# FIT_TCM_SFP_PLUS.net
KiCad netlist of a schematic drawn in Altium Designer
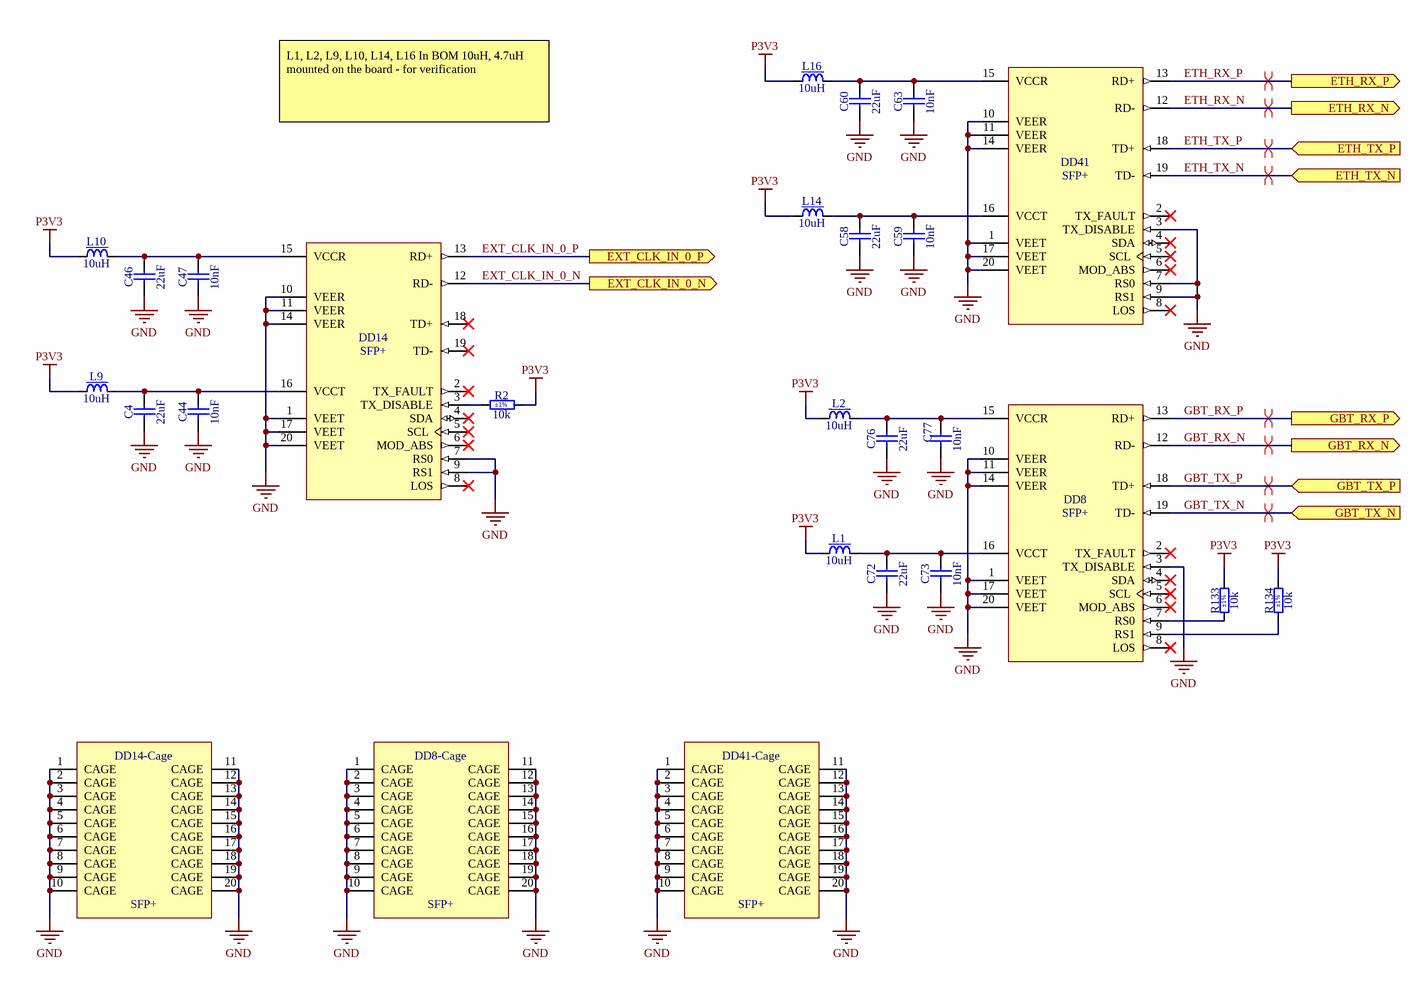
[diagram p0: FIT_TCM_SFP_PLUS.SchDoc]

(export (version "E")
  (design (tool "Eeschema 10.0.6"))
  (components
    (comp (ref "C4")
      (value "22uF")
      (footprint "CAPC3216X180N")
      (description "Non-polarised capacitor")
      (fields
        (field (name "PART NUMBER") "CC1206_22UF_25V_20%_X5R")
        (field (name "VOLTAGE") "25V")
        (field (name "AUTHOR") "CERN DEM WB")
      )
      (libsource (lib "Capacitors") (part "Capacitor - non polarized"))
    )
    (comp (ref "C44")
      (value "10nF")
      (footprint "CAPC2012X135N")
      (description "Non-polarised capacitor")
      (fields
        (field (name "PART NUMBER") "CC0805_10NF_50V_10%_X7R")
        (field (name "VOLTAGE") "50V")
        (field (name "AUTHOR") "CERN DEM JLC")
      )
      (libsource (lib "Capacitors") (part "Capacitor - non polarized"))
    )
    (comp (ref "C46")
      (value "22uF")
      (footprint "CAPC3216X180N")
      (description "Non-polarised capacitor")
      (fields
        (field (name "PART NUMBER") "CC1206_22UF_25V_20%_X5R")
        (field (name "VOLTAGE") "25V")
        (field (name "AUTHOR") "CERN DEM WB")
      )
      (libsource (lib "Capacitors") (part "Capacitor - non polarized"))
    )
    (comp (ref "C47")
      (value "10nF")
      (footprint "CAPC2012X135N")
      (description "Non-polarised capacitor")
      (fields
        (field (name "PART NUMBER") "CC0805_10NF_50V_10%_X7R")
        (field (name "VOLTAGE") "50V")
        (field (name "AUTHOR") "CERN DEM JLC")
      )
      (libsource (lib "Capacitors") (part "Capacitor - non polarized"))
    )
    (comp (ref "C58")
      (value "22uF")
      (footprint "CAPC3216X180N")
      (description "Non-polarised capacitor")
      (fields
        (field (name "PART NUMBER") "CC1206_22UF_25V_20%_X5R")
        (field (name "VOLTAGE") "25V")
        (field (name "AUTHOR") "CERN DEM WB")
      )
      (libsource (lib "Capacitors") (part "Capacitor - non polarized"))
    )
    (comp (ref "C59")
      (value "10nF")
      (footprint "CAPC2012X135N")
      (description "Non-polarised capacitor")
      (fields
        (field (name "PART NUMBER") "CC0805_10NF_50V_10%_X7R")
        (field (name "VOLTAGE") "50V")
        (field (name "AUTHOR") "CERN DEM JLC")
      )
      (libsource (lib "Capacitors") (part "Capacitor - non polarized"))
    )
    (comp (ref "C60")
      (value "22uF")
      (footprint "CAPC3216X180N")
      (description "Non-polarised capacitor")
      (fields
        (field (name "PART NUMBER") "CC1206_22UF_25V_20%_X5R")
        (field (name "VOLTAGE") "25V")
        (field (name "AUTHOR") "CERN DEM WB")
      )
      (libsource (lib "Capacitors") (part "Capacitor - non polarized"))
    )
    (comp (ref "C63")
      (value "10nF")
      (footprint "CAPC2012X135N")
      (description "Non-polarised capacitor")
      (fields
        (field (name "PART NUMBER") "CC0805_10NF_50V_10%_X7R")
        (field (name "VOLTAGE") "50V")
        (field (name "AUTHOR") "CERN DEM JLC")
      )
      (libsource (lib "Capacitors") (part "Capacitor - non polarized"))
    )
    (comp (ref "C72")
      (value "22uF")
      (footprint "CAPC3216X180N")
      (description "Non-polarised capacitor")
      (fields
        (field (name "PART NUMBER") "CC1206_22UF_25V_20%_X5R")
        (field (name "VOLTAGE") "25V")
        (field (name "AUTHOR") "CERN DEM WB")
      )
      (libsource (lib "Capacitors") (part "Capacitor - non polarized"))
    )
    (comp (ref "C73")
      (value "10nF")
      (footprint "CAPC2012X135N")
      (description "Non-polarised capacitor")
      (fields
        (field (name "PART NUMBER") "CC0805_10NF_50V_10%_X7R")
        (field (name "VOLTAGE") "50V")
        (field (name "AUTHOR") "CERN DEM JLC")
      )
      (libsource (lib "Capacitors") (part "Capacitor - non polarized"))
    )
    (comp (ref "C76")
      (value "22uF")
      (footprint "CAPC3216X180N")
      (description "Non-polarised capacitor")
      (fields
        (field (name "PART NUMBER") "CC1206_22UF_25V_20%_X5R")
        (field (name "VOLTAGE") "25V")
        (field (name "AUTHOR") "CERN DEM WB")
      )
      (libsource (lib "Capacitors") (part "Capacitor - non polarized"))
    )
    (comp (ref "C77")
      (value "10nF")
      (footprint "CAPC2012X135N")
      (description "Non-polarised capacitor")
      (fields
        (field (name "PART NUMBER") "CC0805_10NF_50V_10%_X7R")
        (field (name "VOLTAGE") "50V")
        (field (name "AUTHOR") "CERN DEM JLC")
      )
      (libsource (lib "Capacitors") (part "Capacitor - non polarized"))
    )
    (comp (ref "DD8")
      (value "SFP+")
      (footprint "AMPHENOL_UE76A203000")
      (description "20 Position SFP+ Connector (Small Form-factor Pluggable)")
      (fields
        (field (name "PART NUMBER") "AMPHENOL_UE76A203000")
        (field (name "MANUFACTURER") "AMPHENOL")
        (field (name "AUTHOR") "CERN DEM BC")
      )
      (libsource (lib "Connectors") (part "SFP+x1"))
    )
    (comp (ref "DD8-Cage")
      (value "SFP+")
      (footprint "AMPHENOL_U77A16131001")
      (description "SFP+ 1x1 Cage (20Pins)")
      (fields
        (field (name "PART NUMBER") "AMPHENOL_U77A16131001")
        (field (name "MANUFACTURER") "AMPHENOL")
        (field (name "AUTHOR") "CERN DEM BC")
      )
      (libsource (lib "Connectors") (part "SFP+ 1x1 Cage (20Pins)"))
    )
    (comp (ref "DD14")
      (value "SFP+")
      (footprint "AMPHENOL_UE76A203000")
      (description "20 Position SFP+ Connector (Small Form-factor Pluggable)")
      (fields
        (field (name "PART NUMBER") "AMPHENOL_UE76A203000")
        (field (name "MANUFACTURER") "AMPHENOL")
        (field (name "AUTHOR") "CERN DEM BC")
      )
      (libsource (lib "Connectors") (part "SFP+x1"))
    )
    (comp (ref "DD14-Cage")
      (value "SFP+")
      (footprint "AMPHENOL_U77A16131001")
      (description "SFP+ 1x1 Cage (20Pins)")
      (fields
        (field (name "PART NUMBER") "AMPHENOL_U77A16131001")
        (field (name "MANUFACTURER") "AMPHENOL")
        (field (name "AUTHOR") "CERN DEM BC")
      )
      (libsource (lib "Connectors") (part "SFP+ 1x1 Cage (20Pins)"))
    )
    (comp (ref "DD41")
      (value "SFP+")
      (footprint "AMPHENOL_UE76A203000")
      (description "20 Position SFP+ Connector (Small Form-factor Pluggable)")
      (fields
        (field (name "PART NUMBER") "AMPHENOL_UE76A203000")
        (field (name "MANUFACTURER") "AMPHENOL")
        (field (name "AUTHOR") "CERN DEM BC")
      )
      (libsource (lib "Connectors") (part "SFP+x1"))
    )
    (comp (ref "DD41-Cage")
      (value "SFP+")
      (footprint "AMPHENOL_U77A16131001")
      (description "SFP+ 1x1 Cage (20Pins)")
      (fields
        (field (name "PART NUMBER") "AMPHENOL_U77A16131001")
        (field (name "MANUFACTURER") "AMPHENOL")
        (field (name "AUTHOR") "CERN DEM BC")
      )
      (libsource (lib "Connectors") (part "SFP+ 1x1 Cage (20Pins)"))
    )
    (comp (ref "L1")
      (value "10uH")
      (footprint "INDM5552X200N")
      (description "Inductor With Core")
      (fields
        (field (name "PART NUMBER") "IND2020_10UH_20%_VISHAY_IHLP-2020BZ-11")
        (field (name "POWER") "2.2A")
        (field (name "AUTHOR") "CERN DEM HF")
      )
      (libsource (lib "Inductors & Transformers") (part "Inductor With Magnetic core"))
    )
    (comp (ref "L2")
      (value "10uH")
      (footprint "INDM5552X200N")
      (description "Inductor With Core")
      (fields
        (field (name "PART NUMBER") "IND2020_10UH_20%_VISHAY_IHLP-2020BZ-11")
        (field (name "POWER") "2.2A")
        (field (name "AUTHOR") "CERN DEM HF")
      )
      (libsource (lib "Inductors & Transformers") (part "Inductor With Magnetic core"))
    )
    (comp (ref "L9")
      (value "10uH")
      (footprint "INDM5552X200N")
      (description "Inductor With Core")
      (fields
        (field (name "PART NUMBER") "IND2020_10UH_20%_VISHAY_IHLP-2020BZ-11")
        (field (name "POWER") "2.2A")
        (field (name "AUTHOR") "CERN DEM HF")
      )
      (libsource (lib "Inductors & Transformers") (part "Inductor With Magnetic core"))
    )
    (comp (ref "L10")
      (value "10uH")
      (footprint "INDM5552X200N")
      (description "Inductor With Core")
      (fields
        (field (name "PART NUMBER") "IND2020_10UH_20%_VISHAY_IHLP-2020BZ-11")
        (field (name "POWER") "2.2A")
        (field (name "AUTHOR") "CERN DEM HF")
      )
      (libsource (lib "Inductors & Transformers") (part "Inductor With Magnetic core"))
    )
    (comp (ref "L14")
      (value "10uH")
      (footprint "INDM5552X200N")
      (description "Inductor With Core")
      (fields
        (field (name "PART NUMBER") "IND2020_10UH_20%_VISHAY_IHLP-2020BZ-11")
        (field (name "POWER") "2.2A")
        (field (name "AUTHOR") "CERN DEM HF")
      )
      (libsource (lib "Inductors & Transformers") (part "Inductor With Magnetic core"))
    )
    (comp (ref "L16")
      (value "10uH")
      (footprint "INDM5552X200N")
      (description "Inductor With Core")
      (fields
        (field (name "PART NUMBER") "IND2020_10UH_20%_VISHAY_IHLP-2020BZ-11")
        (field (name "POWER") "2.2A")
        (field (name "AUTHOR") "CERN DEM HF")
      )
      (libsource (lib "Inductors & Transformers") (part "Inductor With Magnetic core"))
    )
    (comp (ref "R2")
      (value "10k")
      (footprint "RESC2012X60N")
      (description "Resistor - 1%")
      (fields
        (field (name "TOLERANCE") "±1%")
        (field (name "PART NUMBER") "R0805_10K_1%_0.125W_100PPM")
        (field (name "POWER") "0.125W")
        (field (name "AUTHOR") "CERN DEM JLC")
      )
      (libsource (lib "Resistors") (part "Resistor - 1%"))
    )
    (comp (ref "R133")
      (value "10k")
      (footprint "RESC2012X60N")
      (description "Resistor - 1%")
      (fields
        (field (name "TOLERANCE") "±1%")
        (field (name "PART NUMBER") "R0805_10K_1%_0.125W_100PPM")
        (field (name "POWER") "0.125W")
        (field (name "AUTHOR") "CERN DEM JLC")
      )
      (libsource (lib "Resistors") (part "Resistor - 1%"))
    )
    (comp (ref "R134")
      (value "10k")
      (footprint "RESC2012X60N")
      (description "Resistor - 1%")
      (fields
        (field (name "TOLERANCE") "±1%")
        (field (name "PART NUMBER") "R0805_10K_1%_0.125W_100PPM")
        (field (name "POWER") "0.125W")
        (field (name "AUTHOR") "CERN DEM JLC")
      )
      (libsource (lib "Resistors") (part "Resistor - 1%"))
    )
  )
  (nets
    (net (code "1") (name "/ETH_RX_N") (class "Default")
      (node (ref "DD41") (pin "12") (pinfunction "RD-_12") (pintype "output"))
    )
    (net (code "2") (name "/ETH_RX_P") (class "Default")
      (node (ref "DD41") (pin "13") (pinfunction "RD+_13") (pintype "output"))
    )
    (net (code "3") (name "/ETH_TX_N") (class "Default")
      (node (ref "DD41") (pin "19") (pinfunction "TD-_19") (pintype "input"))
    )
    (net (code "4") (name "/ETH_TX_P") (class "Default")
      (node (ref "DD41") (pin "18") (pinfunction "TD+_18") (pintype "input"))
    )
    (net (code "5") (name "/EXT_CLK_IN_0_N") (class "Default")
      (node (ref "DD14") (pin "12") (pinfunction "RD-_12") (pintype "output"))
    )
    (net (code "6") (name "/EXT_CLK_IN_0_P") (class "Default")
      (node (ref "DD14") (pin "13") (pinfunction "RD+_13") (pintype "output"))
    )
    (net (code "7") (name "/GBT_RX_N") (class "Default")
      (node (ref "DD8") (pin "12") (pinfunction "RD-_12") (pintype "output"))
    )
    (net (code "8") (name "/GBT_RX_P") (class "Default")
      (node (ref "DD8") (pin "13") (pinfunction "RD+_13") (pintype "output"))
    )
    (net (code "9") (name "/GBT_TX_N") (class "Default")
      (node (ref "DD8") (pin "19") (pinfunction "TD-_19") (pintype "input"))
    )
    (net (code "10") (name "/GBT_TX_P") (class "Default")
      (node (ref "DD8") (pin "18") (pinfunction "TD+_18") (pintype "input"))
    )
    (net (code "11") (name "GND") (class "Default")
      (node (ref "C4") (pin "1") (pinfunction "1_1") (pintype "passive"))
      (node (ref "C44") (pin "1") (pinfunction "1_1") (pintype "passive"))
      (node (ref "C46") (pin "1") (pinfunction "1_1") (pintype "passive"))
      (node (ref "C47") (pin "1") (pinfunction "1_1") (pintype "passive"))
      (node (ref "C58") (pin "1") (pinfunction "1_1") (pintype "passive"))
      (node (ref "C59") (pin "1") (pinfunction "1_1") (pintype "passive"))
      (node (ref "C60") (pin "1") (pinfunction "1_1") (pintype "passive"))
      (node (ref "C63") (pin "1") (pinfunction "1_1") (pintype "passive"))
      (node (ref "C72") (pin "1") (pinfunction "1_1") (pintype "passive"))
      (node (ref "C73") (pin "1") (pinfunction "1_1") (pintype "passive"))
      (node (ref "C76") (pin "1") (pinfunction "1_1") (pintype "passive"))
      (node (ref "C77") (pin "1") (pinfunction "1_1") (pintype "passive"))
      (node (ref "DD14") (pin "1") (pinfunction "VEET_1") (pintype "power_in"))
      (node (ref "DD14") (pin "10") (pinfunction "VEER_10") (pintype "power_in"))
      (node (ref "DD14") (pin "11") (pinfunction "VEER_11") (pintype "power_in"))
      (node (ref "DD14") (pin "14") (pinfunction "VEER_14") (pintype "power_in"))
      (node (ref "DD14") (pin "17") (pinfunction "VEET_17") (pintype "power_in"))
      (node (ref "DD14") (pin "20") (pinfunction "VEET_20") (pintype "power_in"))
      (node (ref "DD14") (pin "7") (pinfunction "RS0_7") (pintype "input"))
      (node (ref "DD14") (pin "9") (pinfunction "RS1_9") (pintype "input"))
      (node (ref "DD14-Cage") (pin "1") (pinfunction "CAGE_1") (pintype "power_in"))
      (node (ref "DD14-Cage") (pin "10") (pinfunction "CAGE_10") (pintype "power_in"))
      (node (ref "DD14-Cage") (pin "11") (pinfunction "CAGE_11") (pintype "power_in"))
      (node (ref "DD14-Cage") (pin "12") (pinfunction "CAGE_12") (pintype "power_in"))
      (node (ref "DD14-Cage") (pin "13") (pinfunction "CAGE_13") (pintype "power_in"))
      (node (ref "DD14-Cage") (pin "14") (pinfunction "CAGE_14") (pintype "power_in"))
      (node (ref "DD14-Cage") (pin "15") (pinfunction "CAGE_15") (pintype "power_in"))
      (node (ref "DD14-Cage") (pin "16") (pinfunction "CAGE_16") (pintype "power_in"))
      (node (ref "DD14-Cage") (pin "17") (pinfunction "CAGE_17") (pintype "power_in"))
      (node (ref "DD14-Cage") (pin "18") (pinfunction "CAGE_18") (pintype "power_in"))
      (node (ref "DD14-Cage") (pin "19") (pinfunction "CAGE_19") (pintype "power_in"))
      (node (ref "DD14-Cage") (pin "2") (pinfunction "CAGE_2") (pintype "power_in"))
      (node (ref "DD14-Cage") (pin "20") (pinfunction "CAGE_20") (pintype "power_in"))
      (node (ref "DD14-Cage") (pin "3") (pinfunction "CAGE_3") (pintype "power_in"))
      (node (ref "DD14-Cage") (pin "4") (pinfunction "CAGE_4") (pintype "power_in"))
      (node (ref "DD14-Cage") (pin "5") (pinfunction "CAGE_5") (pintype "power_in"))
      (node (ref "DD14-Cage") (pin "6") (pinfunction "CAGE_6") (pintype "power_in"))
      (node (ref "DD14-Cage") (pin "7") (pinfunction "CAGE_7") (pintype "power_in"))
      (node (ref "DD14-Cage") (pin "8") (pinfunction "CAGE_8") (pintype "power_in"))
      (node (ref "DD14-Cage") (pin "9") (pinfunction "CAGE_9") (pintype "power_in"))
      (node (ref "DD41") (pin "1") (pinfunction "VEET_1") (pintype "power_in"))
      (node (ref "DD41") (pin "10") (pinfunction "VEER_10") (pintype "power_in"))
      (node (ref "DD41") (pin "11") (pinfunction "VEER_11") (pintype "power_in"))
      (node (ref "DD41") (pin "14") (pinfunction "VEER_14") (pintype "power_in"))
      (node (ref "DD41") (pin "17") (pinfunction "VEET_17") (pintype "power_in"))
      (node (ref "DD41") (pin "20") (pinfunction "VEET_20") (pintype "power_in"))
      (node (ref "DD41") (pin "3") (pinfunction "TX_DISABLE_3") (pintype "input"))
      (node (ref "DD41") (pin "7") (pinfunction "RS0_7") (pintype "input"))
      (node (ref "DD41") (pin "9") (pinfunction "RS1_9") (pintype "input"))
      (node (ref "DD41-Cage") (pin "1") (pinfunction "CAGE_1") (pintype "power_in"))
      (node (ref "DD41-Cage") (pin "10") (pinfunction "CAGE_10") (pintype "power_in"))
      (node (ref "DD41-Cage") (pin "11") (pinfunction "CAGE_11") (pintype "power_in"))
      (node (ref "DD41-Cage") (pin "12") (pinfunction "CAGE_12") (pintype "power_in"))
      (node (ref "DD41-Cage") (pin "13") (pinfunction "CAGE_13") (pintype "power_in"))
      (node (ref "DD41-Cage") (pin "14") (pinfunction "CAGE_14") (pintype "power_in"))
      (node (ref "DD41-Cage") (pin "15") (pinfunction "CAGE_15") (pintype "power_in"))
      (node (ref "DD41-Cage") (pin "16") (pinfunction "CAGE_16") (pintype "power_in"))
      (node (ref "DD41-Cage") (pin "17") (pinfunction "CAGE_17") (pintype "power_in"))
      (node (ref "DD41-Cage") (pin "18") (pinfunction "CAGE_18") (pintype "power_in"))
      (node (ref "DD41-Cage") (pin "19") (pinfunction "CAGE_19") (pintype "power_in"))
      (node (ref "DD41-Cage") (pin "2") (pinfunction "CAGE_2") (pintype "power_in"))
      (node (ref "DD41-Cage") (pin "20") (pinfunction "CAGE_20") (pintype "power_in"))
      (node (ref "DD41-Cage") (pin "3") (pinfunction "CAGE_3") (pintype "power_in"))
      (node (ref "DD41-Cage") (pin "4") (pinfunction "CAGE_4") (pintype "power_in"))
      (node (ref "DD41-Cage") (pin "5") (pinfunction "CAGE_5") (pintype "power_in"))
      (node (ref "DD41-Cage") (pin "6") (pinfunction "CAGE_6") (pintype "power_in"))
      (node (ref "DD41-Cage") (pin "7") (pinfunction "CAGE_7") (pintype "power_in"))
      (node (ref "DD41-Cage") (pin "8") (pinfunction "CAGE_8") (pintype "power_in"))
      (node (ref "DD41-Cage") (pin "9") (pinfunction "CAGE_9") (pintype "power_in"))
      (node (ref "DD8") (pin "1") (pinfunction "VEET_1") (pintype "power_in"))
      (node (ref "DD8") (pin "10") (pinfunction "VEER_10") (pintype "power_in"))
      (node (ref "DD8") (pin "11") (pinfunction "VEER_11") (pintype "power_in"))
      (node (ref "DD8") (pin "14") (pinfunction "VEER_14") (pintype "power_in"))
      (node (ref "DD8") (pin "17") (pinfunction "VEET_17") (pintype "power_in"))
      (node (ref "DD8") (pin "20") (pinfunction "VEET_20") (pintype "power_in"))
      (node (ref "DD8") (pin "3") (pinfunction "TX_DISABLE_3") (pintype "input"))
      (node (ref "DD8-Cage") (pin "1") (pinfunction "CAGE_1") (pintype "power_in"))
      (node (ref "DD8-Cage") (pin "10") (pinfunction "CAGE_10") (pintype "power_in"))
      (node (ref "DD8-Cage") (pin "11") (pinfunction "CAGE_11") (pintype "power_in"))
      (node (ref "DD8-Cage") (pin "12") (pinfunction "CAGE_12") (pintype "power_in"))
      (node (ref "DD8-Cage") (pin "13") (pinfunction "CAGE_13") (pintype "power_in"))
      (node (ref "DD8-Cage") (pin "14") (pinfunction "CAGE_14") (pintype "power_in"))
      (node (ref "DD8-Cage") (pin "15") (pinfunction "CAGE_15") (pintype "power_in"))
      (node (ref "DD8-Cage") (pin "16") (pinfunction "CAGE_16") (pintype "power_in"))
      (node (ref "DD8-Cage") (pin "17") (pinfunction "CAGE_17") (pintype "power_in"))
      (node (ref "DD8-Cage") (pin "18") (pinfunction "CAGE_18") (pintype "power_in"))
      (node (ref "DD8-Cage") (pin "19") (pinfunction "CAGE_19") (pintype "power_in"))
      (node (ref "DD8-Cage") (pin "2") (pinfunction "CAGE_2") (pintype "power_in"))
      (node (ref "DD8-Cage") (pin "20") (pinfunction "CAGE_20") (pintype "power_in"))
      (node (ref "DD8-Cage") (pin "3") (pinfunction "CAGE_3") (pintype "power_in"))
      (node (ref "DD8-Cage") (pin "4") (pinfunction "CAGE_4") (pintype "power_in"))
      (node (ref "DD8-Cage") (pin "5") (pinfunction "CAGE_5") (pintype "power_in"))
      (node (ref "DD8-Cage") (pin "6") (pinfunction "CAGE_6") (pintype "power_in"))
      (node (ref "DD8-Cage") (pin "7") (pinfunction "CAGE_7") (pintype "power_in"))
      (node (ref "DD8-Cage") (pin "8") (pinfunction "CAGE_8") (pintype "power_in"))
      (node (ref "DD8-Cage") (pin "9") (pinfunction "CAGE_9") (pintype "power_in"))
    )
    (net (code "12") (name "Net-(DD8-RS0)") (class "Default")
      (node (ref "DD8") (pin "7") (pinfunction "RS0_7") (pintype "input"))
      (node (ref "R133") (pin "1") (pinfunction "1_1") (pintype "passive"))
    )
    (net (code "13") (name "Net-(DD8-RS1)") (class "Default")
      (node (ref "DD8") (pin "9") (pinfunction "RS1_9") (pintype "input"))
      (node (ref "R134") (pin "1") (pinfunction "1_1") (pintype "passive"))
    )
    (net (code "14") (name "Net-(DD8-VCCR)") (class "Default")
      (node (ref "C76") (pin "2") (pinfunction "2_2") (pintype "passive"))
      (node (ref "C77") (pin "2") (pinfunction "2_2") (pintype "passive"))
      (node (ref "DD8") (pin "15") (pinfunction "VCCR_15") (pintype "power_in"))
      (node (ref "L2") (pin "2") (pinfunction "2_2") (pintype "passive"))
    )
    (net (code "15") (name "Net-(DD8-VCCT)") (class "Default")
      (node (ref "C72") (pin "2") (pinfunction "2_2") (pintype "passive"))
      (node (ref "C73") (pin "2") (pinfunction "2_2") (pintype "passive"))
      (node (ref "DD8") (pin "16") (pinfunction "VCCT_16") (pintype "power_in"))
      (node (ref "L1") (pin "2") (pinfunction "2_2") (pintype "passive"))
    )
    (net (code "16") (name "Net-(DD14-TX_DISABLE)") (class "Default")
      (node (ref "DD14") (pin "3") (pinfunction "TX_DISABLE_3") (pintype "input"))
      (node (ref "R2") (pin "1") (pinfunction "1_1") (pintype "passive"))
    )
    (net (code "17") (name "Net-(DD14-VCCR)") (class "Default")
      (node (ref "C46") (pin "2") (pinfunction "2_2") (pintype "passive"))
      (node (ref "C47") (pin "2") (pinfunction "2_2") (pintype "passive"))
      (node (ref "DD14") (pin "15") (pinfunction "VCCR_15") (pintype "power_in"))
      (node (ref "L10") (pin "2") (pinfunction "2_2") (pintype "passive"))
    )
    (net (code "18") (name "Net-(DD14-VCCT)") (class "Default")
      (node (ref "C4") (pin "2") (pinfunction "2_2") (pintype "passive"))
      (node (ref "C44") (pin "2") (pinfunction "2_2") (pintype "passive"))
      (node (ref "DD14") (pin "16") (pinfunction "VCCT_16") (pintype "power_in"))
      (node (ref "L9") (pin "2") (pinfunction "2_2") (pintype "passive"))
    )
    (net (code "19") (name "Net-(DD41-VCCR)") (class "Default")
      (node (ref "C60") (pin "2") (pinfunction "2_2") (pintype "passive"))
      (node (ref "C63") (pin "2") (pinfunction "2_2") (pintype "passive"))
      (node (ref "DD41") (pin "15") (pinfunction "VCCR_15") (pintype "power_in"))
      (node (ref "L16") (pin "2") (pinfunction "2_2") (pintype "passive"))
    )
    (net (code "20") (name "Net-(DD41-VCCT)") (class "Default")
      (node (ref "C58") (pin "2") (pinfunction "2_2") (pintype "passive"))
      (node (ref "C59") (pin "2") (pinfunction "2_2") (pintype "passive"))
      (node (ref "DD41") (pin "16") (pinfunction "VCCT_16") (pintype "power_in"))
      (node (ref "L14") (pin "2") (pinfunction "2_2") (pintype "passive"))
    )
    (net (code "21") (name "P3V3") (class "Default")
      (node (ref "L1") (pin "1") (pinfunction "1_1") (pintype "passive"))
      (node (ref "L10") (pin "1") (pinfunction "1_1") (pintype "passive"))
      (node (ref "L14") (pin "1") (pinfunction "1_1") (pintype "passive"))
      (node (ref "L16") (pin "1") (pinfunction "1_1") (pintype "passive"))
      (node (ref "L2") (pin "1") (pinfunction "1_1") (pintype "passive"))
      (node (ref "L9") (pin "1") (pinfunction "1_1") (pintype "passive"))
      (node (ref "R133") (pin "2") (pinfunction "2_2") (pintype "passive"))
      (node (ref "R134") (pin "2") (pinfunction "2_2") (pintype "passive"))
      (node (ref "R2") (pin "2") (pinfunction "2_2") (pintype "passive"))
    )
    (net (code "22") (name "unconnected-(DD8-LOS-Pad8)") (class "Default")
      (node (ref "DD8") (pin "8") (pinfunction "LOS_8") (pintype "output+no_connect"))
    )
    (net (code "23") (name "unconnected-(DD8-MOD_ABS-Pad6)") (class "Default")
      (node (ref "DD8") (pin "6") (pinfunction "MOD_ABS_6") (pintype "output+no_connect"))
    )
    (net (code "24") (name "unconnected-(DD8-SCL-Pad5)") (class "Default")
      (node (ref "DD8") (pin "5") (pinfunction "SCL_5") (pintype "input+no_connect"))
    )
    (net (code "25") (name "unconnected-(DD8-SDA-Pad4)") (class "Default")
      (node (ref "DD8") (pin "4") (pinfunction "SDA_4") (pintype "bidirectional+no_connect"))
    )
    (net (code "26") (name "unconnected-(DD8-TX_FAULT-Pad2)") (class "Default")
      (node (ref "DD8") (pin "2") (pinfunction "TX_FAULT_2") (pintype "output+no_connect"))
    )
    (net (code "27") (name "unconnected-(DD14-LOS-Pad8)") (class "Default")
      (node (ref "DD14") (pin "8") (pinfunction "LOS_8") (pintype "output+no_connect"))
    )
    (net (code "28") (name "unconnected-(DD14-MOD_ABS-Pad6)") (class "Default")
      (node (ref "DD14") (pin "6") (pinfunction "MOD_ABS_6") (pintype "output+no_connect"))
    )
    (net (code "29") (name "unconnected-(DD14-SCL-Pad5)") (class "Default")
      (node (ref "DD14") (pin "5") (pinfunction "SCL_5") (pintype "input+no_connect"))
    )
    (net (code "30") (name "unconnected-(DD14-SDA-Pad4)") (class "Default")
      (node (ref "DD14") (pin "4") (pinfunction "SDA_4") (pintype "bidirectional+no_connect"))
    )
    (net (code "31") (name "unconnected-(DD14-TD+-Pad18)") (class "Default")
      (node (ref "DD14") (pin "18") (pinfunction "TD+_18") (pintype "input+no_connect"))
    )
    (net (code "32") (name "unconnected-(DD14-TD--Pad19)") (class "Default")
      (node (ref "DD14") (pin "19") (pinfunction "TD-_19") (pintype "input+no_connect"))
    )
    (net (code "33") (name "unconnected-(DD14-TX_FAULT-Pad2)") (class "Default")
      (node (ref "DD14") (pin "2") (pinfunction "TX_FAULT_2") (pintype "output+no_connect"))
    )
    (net (code "34") (name "unconnected-(DD41-LOS-Pad8)") (class "Default")
      (node (ref "DD41") (pin "8") (pinfunction "LOS_8") (pintype "output+no_connect"))
    )
    (net (code "35") (name "unconnected-(DD41-MOD_ABS-Pad6)") (class "Default")
      (node (ref "DD41") (pin "6") (pinfunction "MOD_ABS_6") (pintype "output+no_connect"))
    )
    (net (code "36") (name "unconnected-(DD41-SCL-Pad5)") (class "Default")
      (node (ref "DD41") (pin "5") (pinfunction "SCL_5") (pintype "input+no_connect"))
    )
    (net (code "37") (name "unconnected-(DD41-SDA-Pad4)") (class "Default")
      (node (ref "DD41") (pin "4") (pinfunction "SDA_4") (pintype "bidirectional+no_connect"))
    )
    (net (code "38") (name "unconnected-(DD41-TX_FAULT-Pad2)") (class "Default")
      (node (ref "DD41") (pin "2") (pinfunction "TX_FAULT_2") (pintype "output+no_connect"))
    )
  )
)
